# Power_Supply.net
KiCad netlist of a schematic drawn in Altium Designer
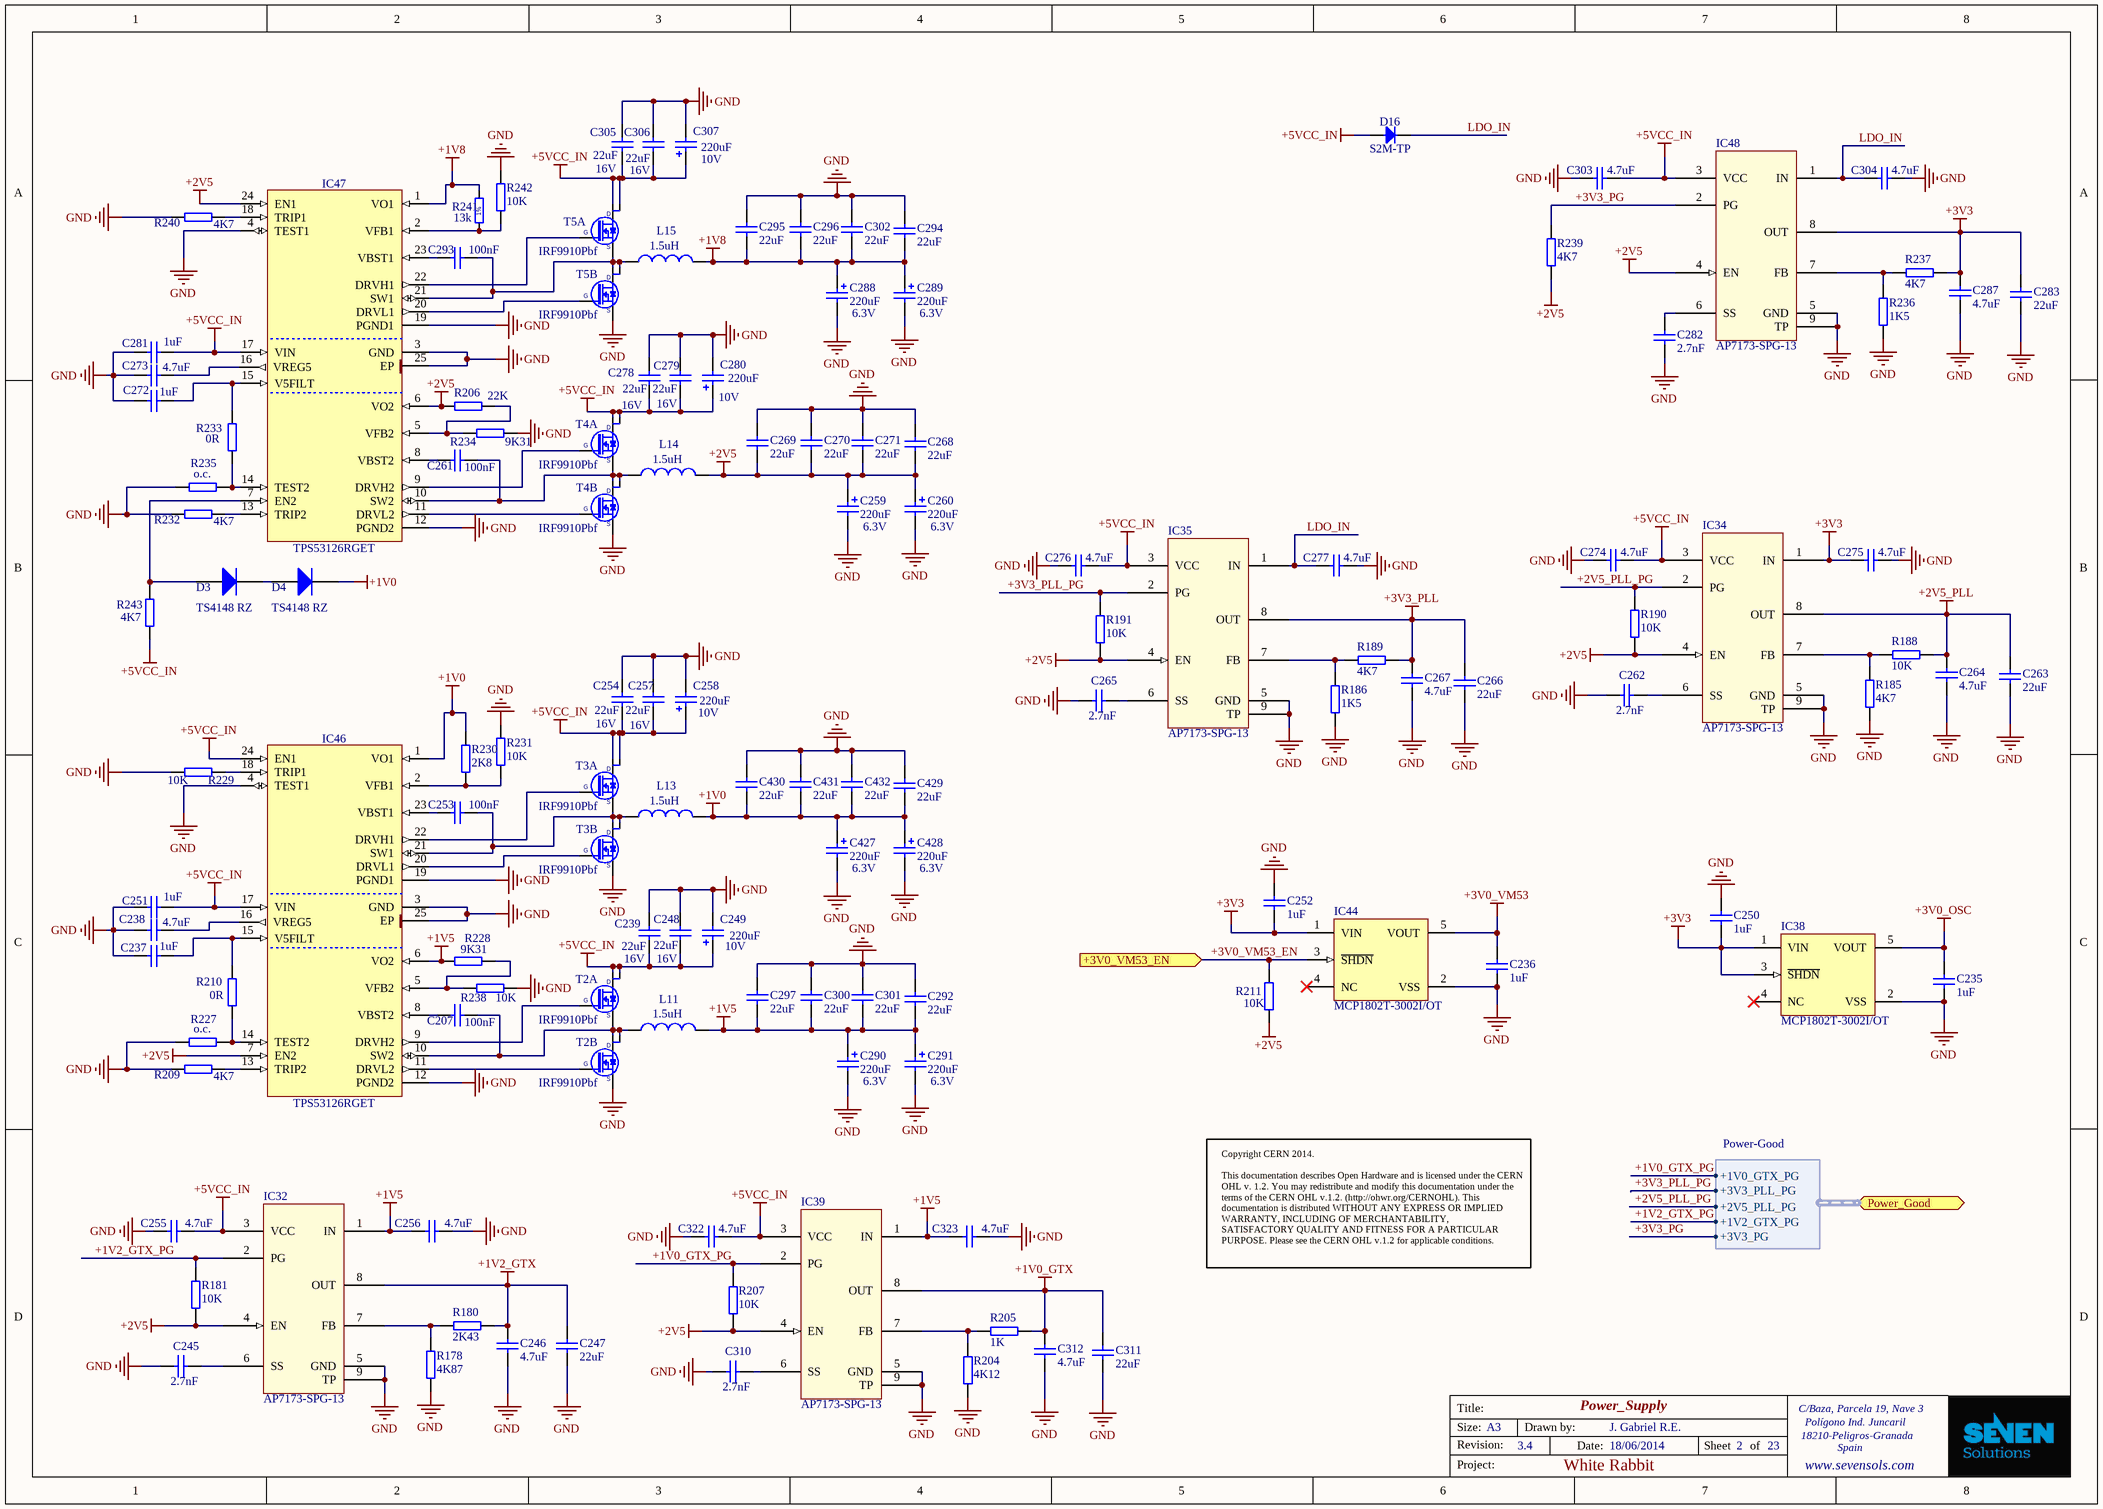
[diagram p0: Power_Supply.SchDoc]

(export (version "E")
  (design (tool "Eeschema 10.0.6"))
  (components
    (comp (ref "C207")
      (value "100nF")
      (footprint "CC1005-0402")
      (description "Capacitor")
      (fields
        (field (name "TOLERANCE") "±10%")
        (field (name "VOLTAGE") "16V")
        (field (name "PUBLISHER") "Altium Limited")
      )
      (libsource (lib "wr_switch") (part "Cap"))
    )
    (comp (ref "C235")
      (value "1uF")
      (footprint "CC1005-0402")
      (description "Capacitor")
      (fields
        (field (name "TOLERANCE") "±10%")
        (field (name "VOLTAGE") "16V")
        (field (name "PUBLISHER") "Altium Limited")
      )
      (libsource (lib "wr_switch") (part "Cap"))
    )
    (comp (ref "C236")
      (value "1uF")
      (footprint "CC1005-0402")
      (description "Capacitor")
      (fields
        (field (name "TOLERANCE") "±10%")
        (field (name "VOLTAGE") "16V")
        (field (name "PUBLISHER") "Altium Limited")
      )
      (libsource (lib "wr_switch") (part "Cap"))
    )
    (comp (ref "C237")
      (value "1uF")
      (footprint "CC1005-0402")
      (description "Capacitor")
      (fields
        (field (name "TOLERANCE") "±10%")
        (field (name "VOLTAGE") "16V")
        (field (name "PUBLISHER") "Altium Limited")
      )
      (libsource (lib "wr_switch") (part "Cap"))
    )
    (comp (ref "C238")
      (value "4.7uF")
      (footprint "CC1608-0603")
      (description "Capacitor")
      (fields
        (field (name "TOLERANCE") "±10%")
        (field (name "VOLTAGE") "10V")
        (field (name "PUBLISHER") "Altium Limited")
      )
      (libsource (lib "wr_switch") (part "Cap"))
    )
    (comp (ref "C239")
      (value "22uF")
      (footprint "CC2012-0805")
      (description "Capacitor")
      (fields
        (field (name "TOLERANCE") "±10%")
        (field (name "VOLTAGE") "16V")
        (field (name "Comment") "22uF 16V")
        (field (name "PUBLISHER") "Altium Limited")
      )
      (libsource (lib "wr_switch") (part "Cap"))
    )
    (comp (ref "C245")
      (value "2.7nF")
      (footprint "CC1005-0402")
      (description "Capacitor")
      (fields
        (field (name "TOLERANCE") "±10%")
        (field (name "VOLTAGE") "50V")
        (field (name "PUBLISHER") "Altium Limited")
      )
      (libsource (lib "wr_switch") (part "Cap"))
    )
    (comp (ref "C246")
      (value "4.7uF")
      (footprint "CC1608-0603")
      (description "Capacitor")
      (fields
        (field (name "TOLERANCE") "±10%")
        (field (name "VOLTAGE") "10V")
        (field (name "PUBLISHER") "Altium Limited")
      )
      (libsource (lib "wr_switch") (part "Cap"))
    )
    (comp (ref "C247")
      (value "22uF")
      (footprint "CC2012-0805")
      (description "Capacitor")
      (fields
        (field (name "TOLERANCE") "±20%")
        (field (name "VOLTAGE") "6.3V")
        (field (name "PUBLISHER") "Altium Limited")
      )
      (libsource (lib "wr_switch") (part "Cap"))
    )
    (comp (ref "C248")
      (value "22uF")
      (footprint "CC2012-0805")
      (description "Capacitor")
      (fields
        (field (name "TOLERANCE") "±10%")
        (field (name "VOLTAGE") "16V")
        (field (name "Comment") "22uF 16V")
        (field (name "PUBLISHER") "Altium Limited")
      )
      (libsource (lib "wr_switch") (part "Cap"))
    )
    (comp (ref "C249")
      (value "220uF")
      (footprint "D")
      (description "Polarized Capacitor Tantalum")
      (fields
        (field (name "TOLERANCE") "±20%")
        (field (name "VOLTAGE") "10V")
        (field (name "Comment") "220uF 10V")
        (field (name "PUBLISHER") "Altium Limited")
      )
      (libsource (lib "wr_switch") (part "Cap Pol1"))
    )
    (comp (ref "C250")
      (value "1uF")
      (footprint "CC1005-0402")
      (description "Capacitor")
      (fields
        (field (name "TOLERANCE") "±10%")
        (field (name "VOLTAGE") "16V")
        (field (name "PUBLISHER") "Altium Limited")
      )
      (libsource (lib "wr_switch") (part "Cap"))
    )
    (comp (ref "C251")
      (value "1uF")
      (footprint "CC1005-0402")
      (description "Capacitor")
      (fields
        (field (name "TOLERANCE") "±10%")
        (field (name "VOLTAGE") "16V")
        (field (name "PUBLISHER") "Altium Limited")
      )
      (libsource (lib "wr_switch") (part "Cap"))
    )
    (comp (ref "C252")
      (value "1uF")
      (footprint "CC1005-0402")
      (description "Capacitor")
      (fields
        (field (name "TOLERANCE") "±10%")
        (field (name "VOLTAGE") "16V")
        (field (name "PUBLISHER") "Altium Limited")
      )
      (libsource (lib "wr_switch") (part "Cap"))
    )
    (comp (ref "C253")
      (value "100nF")
      (footprint "CC1005-0402")
      (description "Capacitor")
      (fields
        (field (name "TOLERANCE") "±10%")
        (field (name "VOLTAGE") "16V")
        (field (name "PUBLISHER") "Altium Limited")
      )
      (libsource (lib "wr_switch") (part "Cap"))
    )
    (comp (ref "C254")
      (value "22uF")
      (footprint "CC2012-0805")
      (description "Capacitor")
      (fields
        (field (name "TOLERANCE") "±10%")
        (field (name "VOLTAGE") "16V")
        (field (name "Comment") "22uF 16V")
        (field (name "PUBLISHER") "Altium Limited")
      )
      (libsource (lib "wr_switch") (part "Cap"))
    )
    (comp (ref "C255")
      (value "4.7uF")
      (footprint "CC1608-0603")
      (description "Capacitor")
      (fields
        (field (name "TOLERANCE") "±10%")
        (field (name "VOLTAGE") "10V")
        (field (name "PUBLISHER") "Altium Limited")
      )
      (libsource (lib "wr_switch") (part "Cap"))
    )
    (comp (ref "C256")
      (value "4.7uF")
      (footprint "CC1608-0603")
      (description "Capacitor")
      (fields
        (field (name "TOLERANCE") "±10%")
        (field (name "VOLTAGE") "10V")
        (field (name "PUBLISHER") "Altium Limited")
      )
      (libsource (lib "wr_switch") (part "Cap"))
    )
    (comp (ref "C257")
      (value "22uF")
      (footprint "CC2012-0805")
      (description "Capacitor")
      (fields
        (field (name "TOLERANCE") "±10%")
        (field (name "VOLTAGE") "16V")
        (field (name "Comment") "22uF 16V")
        (field (name "PUBLISHER") "Altium Limited")
      )
      (libsource (lib "wr_switch") (part "Cap"))
    )
    (comp (ref "C258")
      (value "220uF")
      (footprint "D")
      (description "Polarized Capacitor Tantalum")
      (fields
        (field (name "TOLERANCE") "±20%")
        (field (name "VOLTAGE") "10V")
        (field (name "Comment") "220uF 10V")
        (field (name "PUBLISHER") "Altium Limited")
      )
      (libsource (lib "wr_switch") (part "Cap Pol1"))
    )
    (comp (ref "C259")
      (value "220uF")
      (footprint "D")
      (description "Polarized Capacitor Tantalum")
      (fields
        (field (name "TOLERANCE") "±20%")
        (field (name "VOLTAGE") "6.3V")
        (field (name "PUBLISHER") "Altium Limited")
      )
      (libsource (lib "wr_switch") (part "Cap Pol1"))
    )
    (comp (ref "C260")
      (value "220uF")
      (footprint "D")
      (description "Polarized Capacitor Tantalum")
      (fields
        (field (name "TOLERANCE") "±20%")
        (field (name "VOLTAGE") "6.3V")
        (field (name "PUBLISHER") "Altium Limited")
      )
      (libsource (lib "wr_switch") (part "Cap Pol1"))
    )
    (comp (ref "C261")
      (value "100nF")
      (footprint "CC1005-0402")
      (description "Capacitor")
      (fields
        (field (name "TOLERANCE") "±10%")
        (field (name "VOLTAGE") "16V")
        (field (name "PUBLISHER") "Altium Limited")
      )
      (libsource (lib "wr_switch") (part "Cap"))
    )
    (comp (ref "C262")
      (value "2.7nF")
      (footprint "CC1005-0402")
      (description "Capacitor")
      (fields
        (field (name "TOLERANCE") "±10%")
        (field (name "VOLTAGE") "50V")
        (field (name "PUBLISHER") "Altium Limited")
      )
      (libsource (lib "wr_switch") (part "Cap"))
    )
    (comp (ref "C263")
      (value "22uF")
      (footprint "CC2012-0805")
      (description "Capacitor")
      (fields
        (field (name "TOLERANCE") "±20%")
        (field (name "VOLTAGE") "6.3V")
        (field (name "PUBLISHER") "Altium Limited")
      )
      (libsource (lib "wr_switch") (part "Cap"))
    )
    (comp (ref "C264")
      (value "4.7uF")
      (footprint "CC1608-0603")
      (description "Capacitor")
      (fields
        (field (name "TOLERANCE") "±10%")
        (field (name "VOLTAGE") "10V")
        (field (name "PUBLISHER") "Altium Limited")
      )
      (libsource (lib "wr_switch") (part "Cap"))
    )
    (comp (ref "C265")
      (value "2.7nF")
      (footprint "CC1005-0402")
      (description "Capacitor")
      (fields
        (field (name "TOLERANCE") "±10%")
        (field (name "VOLTAGE") "50V")
        (field (name "PUBLISHER") "Altium Limited")
      )
      (libsource (lib "wr_switch") (part "Cap"))
    )
    (comp (ref "C266")
      (value "22uF")
      (footprint "CC2012-0805")
      (description "Capacitor")
      (fields
        (field (name "TOLERANCE") "±20%")
        (field (name "VOLTAGE") "6.3V")
        (field (name "PUBLISHER") "Altium Limited")
      )
      (libsource (lib "wr_switch") (part "Cap"))
    )
    (comp (ref "C267")
      (value "4.7uF")
      (footprint "CC1608-0603")
      (description "Capacitor")
      (fields
        (field (name "TOLERANCE") "±10%")
        (field (name "VOLTAGE") "10V")
        (field (name "PUBLISHER") "Altium Limited")
      )
      (libsource (lib "wr_switch") (part "Cap"))
    )
    (comp (ref "C268")
      (value "22uF")
      (footprint "CC2012-0805")
      (description "Capacitor")
      (fields
        (field (name "TOLERANCE") "±20%")
        (field (name "VOLTAGE") "6.3V")
        (field (name "PUBLISHER") "Altium Limited")
      )
      (libsource (lib "wr_switch") (part "Cap"))
    )
    (comp (ref "C269")
      (value "22uF")
      (footprint "CC2012-0805")
      (description "Capacitor")
      (fields
        (field (name "TOLERANCE") "±20%")
        (field (name "VOLTAGE") "6.3V")
        (field (name "PUBLISHER") "Altium Limited")
      )
      (libsource (lib "wr_switch") (part "Cap"))
    )
    (comp (ref "C270")
      (value "22uF")
      (footprint "CC2012-0805")
      (description "Capacitor")
      (fields
        (field (name "TOLERANCE") "±20%")
        (field (name "VOLTAGE") "6.3V")
        (field (name "PUBLISHER") "Altium Limited")
      )
      (libsource (lib "wr_switch") (part "Cap"))
    )
    (comp (ref "C271")
      (value "22uF")
      (footprint "CC2012-0805")
      (description "Capacitor")
      (fields
        (field (name "TOLERANCE") "±20%")
        (field (name "VOLTAGE") "6.3V")
        (field (name "PUBLISHER") "Altium Limited")
      )
      (libsource (lib "wr_switch") (part "Cap"))
    )
    (comp (ref "C272")
      (value "1uF")
      (footprint "CC1005-0402")
      (description "Capacitor")
      (fields
        (field (name "TOLERANCE") "±10%")
        (field (name "VOLTAGE") "16V")
        (field (name "PUBLISHER") "Altium Limited")
      )
      (libsource (lib "wr_switch") (part "Cap"))
    )
    (comp (ref "C273")
      (value "4.7uF")
      (footprint "CC1608-0603")
      (description "Capacitor")
      (fields
        (field (name "TOLERANCE") "±10%")
        (field (name "VOLTAGE") "10V")
        (field (name "PUBLISHER") "Altium Limited")
      )
      (libsource (lib "wr_switch") (part "Cap"))
    )
    (comp (ref "C274")
      (value "4.7uF")
      (footprint "CC1608-0603")
      (description "Capacitor")
      (fields
        (field (name "TOLERANCE") "±10%")
        (field (name "VOLTAGE") "10V")
        (field (name "PUBLISHER") "Altium Limited")
      )
      (libsource (lib "wr_switch") (part "Cap"))
    )
    (comp (ref "C275")
      (value "4.7uF")
      (footprint "CC1608-0603")
      (description "Capacitor")
      (fields
        (field (name "TOLERANCE") "±10%")
        (field (name "VOLTAGE") "10V")
        (field (name "PUBLISHER") "Altium Limited")
      )
      (libsource (lib "wr_switch") (part "Cap"))
    )
    (comp (ref "C276")
      (value "4.7uF")
      (footprint "CC1608-0603")
      (description "Capacitor")
      (fields
        (field (name "TOLERANCE") "±10%")
        (field (name "VOLTAGE") "10V")
        (field (name "PUBLISHER") "Altium Limited")
      )
      (libsource (lib "wr_switch") (part "Cap"))
    )
    (comp (ref "C277")
      (value "4.7uF")
      (footprint "CC1608-0603")
      (description "Capacitor")
      (fields
        (field (name "TOLERANCE") "±10%")
        (field (name "VOLTAGE") "10V")
        (field (name "PUBLISHER") "Altium Limited")
      )
      (libsource (lib "wr_switch") (part "Cap"))
    )
    (comp (ref "C278")
      (value "22uF")
      (footprint "CC2012-0805")
      (description "Capacitor")
      (fields
        (field (name "TOLERANCE") "±10%")
        (field (name "VOLTAGE") "16V")
        (field (name "Comment") "22uF 16V")
        (field (name "PUBLISHER") "Altium Limited")
      )
      (libsource (lib "wr_switch") (part "Cap"))
    )
    (comp (ref "C279")
      (value "22uF")
      (footprint "CC2012-0805")
      (description "Capacitor")
      (fields
        (field (name "TOLERANCE") "±10%")
        (field (name "VOLTAGE") "16V")
        (field (name "Comment") "22uF 16V")
        (field (name "PUBLISHER") "Altium Limited")
      )
      (libsource (lib "wr_switch") (part "Cap"))
    )
    (comp (ref "C280")
      (value "220uF")
      (footprint "D")
      (description "Polarized Capacitor Tantalum")
      (fields
        (field (name "TOLERANCE") "±20%")
        (field (name "VOLTAGE") "10V")
        (field (name "Comment") "220uF 10V")
        (field (name "PUBLISHER") "Altium Limited")
      )
      (libsource (lib "wr_switch") (part "Cap Pol1"))
    )
    (comp (ref "C281")
      (value "1uF")
      (footprint "CC1005-0402")
      (description "Capacitor")
      (fields
        (field (name "TOLERANCE") "±10%")
        (field (name "VOLTAGE") "16V")
        (field (name "PUBLISHER") "Altium Limited")
      )
      (libsource (lib "wr_switch") (part "Cap"))
    )
    (comp (ref "C282")
      (value "2.7nF")
      (footprint "CC1005-0402")
      (description "Capacitor")
      (fields
        (field (name "TOLERANCE") "±10%")
        (field (name "VOLTAGE") "50V")
        (field (name "PUBLISHER") "Altium Limited")
      )
      (libsource (lib "wr_switch") (part "Cap"))
    )
    (comp (ref "C283")
      (value "22uF")
      (footprint "CC2012-0805")
      (description "Capacitor")
      (fields
        (field (name "TOLERANCE") "±20%")
        (field (name "VOLTAGE") "6.3V")
        (field (name "PUBLISHER") "Altium Limited")
      )
      (libsource (lib "wr_switch") (part "Cap"))
    )
    (comp (ref "C287")
      (value "4.7uF")
      (footprint "CC1608-0603")
      (description "Capacitor")
      (fields
        (field (name "TOLERANCE") "±10%")
        (field (name "VOLTAGE") "10V")
        (field (name "PUBLISHER") "Altium Limited")
      )
      (libsource (lib "wr_switch") (part "Cap"))
    )
    (comp (ref "C288")
      (value "220uF")
      (footprint "D")
      (description "Polarized Capacitor Tantalum")
      (fields
        (field (name "TOLERANCE") "±20%")
        (field (name "VOLTAGE") "6.3V")
        (field (name "PUBLISHER") "Altium Limited")
      )
      (libsource (lib "wr_switch") (part "Cap Pol1"))
    )
    (comp (ref "C289")
      (value "220uF")
      (footprint "D")
      (description "Polarized Capacitor Tantalum")
      (fields
        (field (name "TOLERANCE") "±20%")
        (field (name "VOLTAGE") "6.3V")
        (field (name "PUBLISHER") "Altium Limited")
      )
      (libsource (lib "wr_switch") (part "Cap Pol1"))
    )
    (comp (ref "C290")
      (value "220uF")
      (footprint "D")
      (description "Polarized Capacitor Tantalum")
      (fields
        (field (name "TOLERANCE") "±20%")
        (field (name "VOLTAGE") "6.3V")
        (field (name "PUBLISHER") "Altium Limited")
      )
      (libsource (lib "wr_switch") (part "Cap Pol1"))
    )
    (comp (ref "C291")
      (value "220uF")
      (footprint "D")
      (description "Polarized Capacitor Tantalum")
      (fields
        (field (name "TOLERANCE") "±20%")
        (field (name "VOLTAGE") "6.3V")
        (field (name "PUBLISHER") "Altium Limited")
      )
      (libsource (lib "wr_switch") (part "Cap Pol1"))
    )
    (comp (ref "C292")
      (value "22uF")
      (footprint "CC2012-0805")
      (description "Capacitor")
      (fields
        (field (name "TOLERANCE") "±20%")
        (field (name "VOLTAGE") "6.3V")
        (field (name "PUBLISHER") "Altium Limited")
      )
      (libsource (lib "wr_switch") (part "Cap"))
    )
    (comp (ref "C293")
      (value "100nF")
      (footprint "CC1005-0402")
      (description "Capacitor")
      (fields
        (field (name "TOLERANCE") "±10%")
        (field (name "VOLTAGE") "16V")
        (field (name "PUBLISHER") "Altium Limited")
      )
      (libsource (lib "wr_switch") (part "Cap"))
    )
    (comp (ref "C294")
      (value "22uF")
      (footprint "CC2012-0805")
      (description "Capacitor")
      (fields
        (field (name "TOLERANCE") "±20%")
        (field (name "VOLTAGE") "6.3V")
        (field (name "PUBLISHER") "Altium Limited")
      )
      (libsource (lib "wr_switch") (part "Cap"))
    )
    (comp (ref "C295")
      (value "22uF")
      (footprint "CC2012-0805")
      (description "Capacitor")
      (fields
        (field (name "TOLERANCE") "±20%")
        (field (name "VOLTAGE") "6.3V")
        (field (name "PUBLISHER") "Altium Limited")
      )
      (libsource (lib "wr_switch") (part "Cap"))
    )
    (comp (ref "C296")
      (value "22uF")
      (footprint "CC2012-0805")
      (description "Capacitor")
      (fields
        (field (name "TOLERANCE") "±20%")
        (field (name "VOLTAGE") "6.3V")
        (field (name "PUBLISHER") "Altium Limited")
      )
      (libsource (lib "wr_switch") (part "Cap"))
    )
    (comp (ref "C297")
      (value "22uF")
      (footprint "CC2012-0805")
      (description "Capacitor")
      (fields
        (field (name "TOLERANCE") "±20%")
        (field (name "VOLTAGE") "6.3V")
        (field (name "PUBLISHER") "Altium Limited")
      )
      (libsource (lib "wr_switch") (part "Cap"))
    )
    (comp (ref "C300")
      (value "22uF")
      (footprint "CC2012-0805")
      (description "Capacitor")
      (fields
        (field (name "TOLERANCE") "±20%")
        (field (name "VOLTAGE") "6.3V")
        (field (name "PUBLISHER") "Altium Limited")
      )
      (libsource (lib "wr_switch") (part "Cap"))
    )
    (comp (ref "C301")
      (value "22uF")
      (footprint "CC2012-0805")
      (description "Capacitor")
      (fields
        (field (name "TOLERANCE") "±20%")
        (field (name "VOLTAGE") "6.3V")
        (field (name "PUBLISHER") "Altium Limited")
      )
      (libsource (lib "wr_switch") (part "Cap"))
    )
    (comp (ref "C302")
      (value "22uF")
      (footprint "CC2012-0805")
      (description "Capacitor")
      (fields
        (field (name "TOLERANCE") "±20%")
        (field (name "VOLTAGE") "6.3V")
        (field (name "PUBLISHER") "Altium Limited")
      )
      (libsource (lib "wr_switch") (part "Cap"))
    )
    (comp (ref "C303")
      (value "4.7uF")
      (footprint "CC1608-0603")
      (description "Capacitor")
      (fields
        (field (name "TOLERANCE") "±10%")
        (field (name "VOLTAGE") "10V")
        (field (name "PUBLISHER") "Altium Limited")
      )
      (libsource (lib "wr_switch") (part "Cap"))
    )
    (comp (ref "C304")
      (value "4.7uF")
      (footprint "CC1608-0603")
      (description "Capacitor")
      (fields
        (field (name "TOLERANCE") "±10%")
        (field (name "VOLTAGE") "10V")
        (field (name "PUBLISHER") "Altium Limited")
      )
      (libsource (lib "wr_switch") (part "Cap"))
    )
    (comp (ref "C305")
      (value "22uF")
      (footprint "CC2012-0805")
      (description "Capacitor")
      (fields
        (field (name "TOLERANCE") "±10%")
        (field (name "VOLTAGE") "16V")
        (field (name "Comment") "22uF 16V")
        (field (name "PUBLISHER") "Altium Limited")
      )
      (libsource (lib "wr_switch") (part "Cap"))
    )
    (comp (ref "C306")
      (value "22uF")
      (footprint "CC2012-0805")
      (description "Capacitor")
      (fields
        (field (name "TOLERANCE") "±10%")
        (field (name "VOLTAGE") "16V")
        (field (name "Comment") "22uF 16V")
        (field (name "PUBLISHER") "Altium Limited")
      )
      (libsource (lib "wr_switch") (part "Cap"))
    )
    (comp (ref "C307")
      (value "220uF")
      (footprint "D")
      (description "Polarized Capacitor Tantalum")
      (fields
        (field (name "TOLERANCE") "±20%")
        (field (name "VOLTAGE") "10V")
        (field (name "Comment") "220uF 10V")
        (field (name "PUBLISHER") "Altium Limited")
      )
      (libsource (lib "wr_switch") (part "Cap Pol1"))
    )
    (comp (ref "C310")
      (value "2.7nF")
      (footprint "CC1005-0402")
      (description "Capacitor")
      (fields
        (field (name "TOLERANCE") "±10%")
        (field (name "VOLTAGE") "50V")
        (field (name "PUBLISHER") "Altium Limited")
      )
      (libsource (lib "wr_switch") (part "Cap"))
    )
    (comp (ref "C311")
      (value "22uF")
      (footprint "CC2012-0805")
      (description "Capacitor")
      (fields
        (field (name "TOLERANCE") "±20%")
        (field (name "VOLTAGE") "6.3V")
        (field (name "PUBLISHER") "Altium Limited")
      )
      (libsource (lib "wr_switch") (part "Cap"))
    )
    (comp (ref "C312")
      (value "4.7uF")
      (footprint "CC1608-0603")
      (description "Capacitor")
      (fields
        (field (name "TOLERANCE") "±10%")
        (field (name "VOLTAGE") "10V")
        (field (name "PUBLISHER") "Altium Limited")
      )
      (libsource (lib "wr_switch") (part "Cap"))
    )
    (comp (ref "C322")
      (value "4.7uF")
      (footprint "CC1608-0603")
      (description "Capacitor")
      (fields
        (field (name "TOLERANCE") "±10%")
        (field (name "VOLTAGE") "10V")
        (field (name "PUBLISHER") "Altium Limited")
      )
      (libsource (lib "wr_switch") (part "Cap"))
    )
    (comp (ref "C323")
      (value "4.7uF")
      (footprint "CC1608-0603")
      (description "Capacitor")
      (fields
        (field (name "TOLERANCE") "±10%")
        (field (name "VOLTAGE") "10V")
        (field (name "PUBLISHER") "Altium Limited")
      )
      (libsource (lib "wr_switch") (part "Cap"))
    )
    (comp (ref "C427")
      (value "220uF")
      (footprint "D")
      (description "Polarized Capacitor Tantalum")
      (fields
        (field (name "TOLERANCE") "±20%")
        (field (name "VOLTAGE") "6.3V")
        (field (name "PUBLISHER") "Altium Limited")
      )
      (libsource (lib "wr_switch") (part "Cap Pol1"))
    )
    (comp (ref "C428")
      (value "220uF")
      (footprint "D")
      (description "Polarized Capacitor Tantalum")
      (fields
        (field (name "TOLERANCE") "±20%")
        (field (name "VOLTAGE") "6.3V")
        (field (name "PUBLISHER") "Altium Limited")
      )
      (libsource (lib "wr_switch") (part "Cap Pol1"))
    )
    (comp (ref "C429")
      (value "22uF")
      (footprint "CC2012-0805")
      (description "Capacitor")
      (fields
        (field (name "TOLERANCE") "±20%")
        (field (name "VOLTAGE") "6.3V")
        (field (name "PUBLISHER") "Altium Limited")
      )
      (libsource (lib "wr_switch") (part "Cap"))
    )
    (comp (ref "C430")
      (value "22uF")
      (footprint "CC2012-0805")
      (description "Capacitor")
      (fields
        (field (name "TOLERANCE") "±20%")
        (field (name "VOLTAGE") "6.3V")
        (field (name "PUBLISHER") "Altium Limited")
      )
      (libsource (lib "wr_switch") (part "Cap"))
    )
    (comp (ref "C431")
      (value "22uF")
      (footprint "CC2012-0805")
      (description "Capacitor")
      (fields
        (field (name "TOLERANCE") "±20%")
        (field (name "VOLTAGE") "6.3V")
        (field (name "PUBLISHER") "Altium Limited")
      )
      (libsource (lib "wr_switch") (part "Cap"))
    )
    (comp (ref "C432")
      (value "22uF")
      (footprint "CC2012-0805")
      (description "Capacitor")
      (fields
        (field (name "TOLERANCE") "±20%")
        (field (name "VOLTAGE") "6.3V")
        (field (name "PUBLISHER") "Altium Limited")
      )
      (libsource (lib "wr_switch") (part "Cap"))
    )
    (comp (ref "D3")
      (value "TS4148 RZ")
      (footprint "CD1608-0603")
      (description "Default Diode")
      (fields (field (name "PUBLISHER") "Altium Limited"))
      (libsource (lib "Miscellaneous Devices") (part "Diode"))
    )
    (comp (ref "D4")
      (value "TS4148 RZ")
      (footprint "CD1608-0603")
      (description "Default Diode")
      (fields (field (name "PUBLISHER") "Altium Limited"))
      (libsource (lib "Miscellaneous Devices") (part "Diode"))
    )
    (comp (ref "D16")
      (value "S2M-TP")
      (footprint "DO-214AA/SMB-MCC")
      (description "2 A Silicon Rectifier 50 to 1000 Volts")
      (fields (field (name "AUTHOR") "CERN DEM JLC"))
      (libsource (lib "wr_switch") (part "S2M-TP"))
    )
    (comp (ref "IC32")
      (value "AP7173-SPG-13")
      (footprint "7S_WR:SOIC127P600-8AL-ThermalPad")
      (description "1.5A Low Dropout Linera Regulator")
      (libsource (lib "SCB") (part "AP7173"))
    )
    (comp (ref "IC34")
      (value "AP7173-SPG-13")
      (footprint "7S_WR:SOIC127P600-8AL-ThermalPad")
      (description "1.5A Low Dropout Linera Regulator")
      (libsource (lib "SCB") (part "AP7173"))
    )
    (comp (ref "IC35")
      (value "AP7173-SPG-13")
      (footprint "7S_WR:SOIC127P600-8AL-ThermalPad")
      (description "1.5A Low Dropout Linera Regulator")
      (libsource (lib "SCB") (part "AP7173"))
    )
    (comp (ref "IC38")
      (value "MCP1802T-3002I/OT")
      (footprint "SOT-23-OT5_N")
      (description "300 mA, High PSRR, Low Quiescent Current LDO, 5-Pin SOT-23, Industrial Temperature, Tape and Reel")
      (fields (field (name "PUBLISHER") "Altium Limited"))
      (libsource (lib "Microchip Power Mgt Line Regulator") (part "MCP1802T-3002I/OT"))
    )
    (comp (ref "IC39")
      (value "AP7173-SPG-13")
      (footprint "7S_WR:SOIC127P600-8AL-ThermalPad")
      (description "1.5A Low Dropout Linera Regulator")
      (libsource (lib "SCB") (part "AP7173"))
    )
    (comp (ref "IC44")
      (value "MCP1802T-3002I/OT")
      (footprint "SOT-23-OT5_N")
      (description "300 mA, High PSRR, Low Quiescent Current LDO, 5-Pin SOT-23, Industrial Temperature, Tape and Reel")
      (fields (field (name "PUBLISHER") "Altium Limited"))
      (libsource (lib "Microchip Power Mgt Line Regulator") (part "MCP1802T-3002I/OT"))
    )
    (comp (ref "IC46")
      (value "TPS53126RGET")
      (footprint "QFN50P400X400X100-25N-S255")
      (description "Dual Synchronous Step-Down Controller For Low Voltage Power Rails")
      (fields (field (name "MANUFACTURER") "TEXAS INSTRUMENTS") (field (name "AUTHOR") "CERN DEM JLC"))
      (libsource (lib "wr_switch") (part "TPS53126RGET"))
    )
    (comp (ref "IC47")
      (value "TPS53126RGET")
      (footprint "QFN50P400X400X100-25N-S255")
      (description "Dual Synchronous Step-Down Controller For Low Voltage Power Rails")
      (fields (field (name "MANUFACTURER") "TEXAS INSTRUMENTS") (field (name "AUTHOR") "CERN DEM JLC"))
      (libsource (lib "wr_switch") (part "TPS53126RGET"))
    )
    (comp (ref "IC48")
      (value "AP7173-SPG-13")
      (footprint "7S_WR:SOIC127P600-8AL-ThermalPad")
      (description "1.5A Low Dropout Linera Regulator")
      (libsource (lib "SCB") (part "AP7173"))
    )
    (comp (ref "L11")
      (value "1.5uH")
      (footprint "IHLP2525")
      (description "Low Profile, High Current Inductor")
      (fields
        (field (name "MANUFACTURER") "Vishay/Dale")
        (field (name "Comment") "IHLP2525CZER1R5M01")
        (field (name "PUBLISHER") "Altium Limited")
      )
      (libsource (lib "Miscellaneous Devices") (part "Inductor"))
    )
    (comp (ref "L13")
      (value "1.5uH")
      (footprint "IHLP2525")
      (description "Low Profile, High Current Inductor")
      (fields
        (field (name "MANUFACTURER") "Vishay/Dale")
        (field (name "Comment") "IHLP2525CZER1R5M01")
        (field (name "PUBLISHER") "Altium Limited")
      )
      (libsource (lib "Miscellaneous Devices") (part "Inductor"))
    )
    (comp (ref "L14")
      (value "1.5uH")
      (footprint "IHLP2525")
      (description "Low Profile, High Current Inductor")
      (fields
        (field (name "MANUFACTURER") "Vishay/Dale")
        (field (name "Comment") "IHLP2525CZER1R5M01")
        (field (name "PUBLISHER") "Altium Limited")
      )
      (libsource (lib "Miscellaneous Devices") (part "Inductor"))
    )
    (comp (ref "L15")
      (value "1.5uH")
      (footprint "IHLP2525")
      (description "Low Profile, High Current Inductor")
      (fields
        (field (name "MANUFACTURER") "Vishay/Dale")
        (field (name "Comment") "IHLP2525CZER1R5M01")
        (field (name "PUBLISHER") "Altium Limited")
      )
      (libsource (lib "Miscellaneous Devices") (part "Inductor"))
    )
    (comp (ref "R178")
      (value "4K87")
      (footprint "0402")
      (description "SMD Resistor")
      (fields (field (name "TOLERANCE") "±1%"))
      (libsource (lib "wr_switch") (part "RES_SMD"))
    )
    (comp (ref "R180")
      (value "2K43")
      (footprint "0402")
      (description "SMD Resistor")
      (fields (field (name "TOLERANCE") "±1%"))
      (libsource (lib "wr_switch") (part "RES_SMD"))
    )
    (comp (ref "R181")
      (value "10K")
      (footprint "0402")
      (description "SMD Resistor")
      (fields (field (name "TOLERANCE") "±1%") (field (name "Comment") "10k"))
      (libsource (lib "wr_switch") (part "RES_SMD"))
    )
    (comp (ref "R185")
      (value "4K7")
      (footprint "0402")
      (description "SMD Resistor")
      (fields (field (name "TOLERANCE") "±1%"))
      (libsource (lib "wr_switch") (part "RES_SMD"))
    )
    (comp (ref "R186")
      (value "1K5")
      (footprint "0402")
      (description "SMD Resistor")
      (fields (field (name "TOLERANCE") "±1%"))
      (libsource (lib "wr_switch") (part "RES_SMD"))
    )
    (comp (ref "R188")
      (value "10K")
      (footprint "0402")
      (description "SMD Resistor")
      (fields (field (name "TOLERANCE") "±1%"))
      (libsource (lib "wr_switch") (part "RES_SMD"))
    )
    (comp (ref "R189")
      (value "4K7")
      (footprint "0402")
      (description "SMD Resistor")
      (fields (field (name "TOLERANCE") "±1%"))
      (libsource (lib "wr_switch") (part "RES_SMD"))
    )
    (comp (ref "R190")
      (value "10K")
      (footprint "0402")
      (description "SMD Resistor")
      (fields (field (name "TOLERANCE") "±1%") (field (name "Comment") "10k"))
      (libsource (lib "wr_switch") (part "RES_SMD"))
    )
    (comp (ref "R191")
      (value "10K")
      (footprint "0402")
      (description "SMD Resistor")
      (fields (field (name "TOLERANCE") "±1%") (field (name "Comment") "10k"))
      (libsource (lib "wr_switch") (part "RES_SMD"))
    )
    (comp (ref "R204")
      (value "4K12")
      (footprint "0402")
      (description "SMD Resistor")
      (fields (field (name "TOLERANCE") "±1%"))
      (libsource (lib "wr_switch") (part "RES_SMD"))
    )
    (comp (ref "R205")
      (value "1K")
      (footprint "0402")
      (description "SMD Resistor")
      (fields (field (name "TOLERANCE") "±1%"))
      (libsource (lib "wr_switch") (part "RES_SMD"))
    )
    (comp (ref "R206")
      (value "22K")
      (footprint "0402")
      (description "SMD Resistor")
      (fields (field (name "TOLERANCE") "±1%"))
      (libsource (lib "wr_switch") (part "RES_SMD"))
    )
    (comp (ref "R207")
      (value "10K")
      (footprint "0402")
      (description "SMD Resistor")
      (fields (field (name "TOLERANCE") "±1%"))
      (libsource (lib "wr_switch") (part "RES_SMD"))
    )
    (comp (ref "R209")
      (value "4K7")
      (footprint "0402")
      (description "SMD Resistor")
      (fields (field (name "TOLERANCE") "±1%"))
      (libsource (lib "wr_switch") (part "RES_SMD"))
    )
    (comp (ref "R210")
      (value "0R")
      (footprint "0402")
      (description "SMD Resistor")
      (fields (field (name "TOLERANCE") "Jumper"))
      (libsource (lib "wr_switch") (part "RES_SMD"))
    )
    (comp (ref "R211")
      (value "10K")
      (footprint "0402")
      (description "SMD Resistor")
      (fields (field (name "TOLERANCE") "±1%") (field (name "Comment") "10k"))
      (libsource (lib "wr_switch") (part "RES_SMD"))
    )
    (comp (ref "R227")
      (value "o.c.")
      (footprint "0402")
      (description "SMD Resistor")
      (libsource (lib "wr_switch") (part "RES_SMD"))
    )
    (comp (ref "R228")
      (value "9K31")
      (footprint "0402")
      (description "SMD Resistor")
      (fields (field (name "TOLERANCE") "±1%"))
      (libsource (lib "wr_switch") (part "RES_SMD"))
    )
    (comp (ref "R229")
      (value "10K")
      (footprint "0402")
      (description "SMD Resistor")
      (fields (field (name "TOLERANCE") "±1%"))
      (libsource (lib "wr_switch") (part "RES_SMD"))
    )
    (comp (ref "R230")
      (value "2K8")
      (footprint "0402")
      (description "SMD Resistor")
      (fields (field (name "TOLERANCE") "±1%"))
      (libsource (lib "wr_switch") (part "RES_SMD"))
    )
    (comp (ref "R231")
      (value "10K")
      (footprint "0402")
      (description "SMD Resistor")
      (fields (field (name "TOLERANCE") "±1%"))
      (libsource (lib "wr_switch") (part "RES_SMD"))
    )
    (comp (ref "R232")
      (value "4K7")
      (footprint "0402")
      (description "SMD Resistor")
      (fields (field (name "TOLERANCE") "±1%"))
      (libsource (lib "wr_switch") (part "RES_SMD"))
    )
    (comp (ref "R233")
      (value "0R")
      (footprint "0402")
      (description "SMD Resistor")
      (fields (field (name "TOLERANCE") "Jumper"))
      (libsource (lib "wr_switch") (part "RES_SMD"))
    )
    (comp (ref "R234")
      (value "9K31")
      (footprint "0402")
      (description "SMD Resistor")
      (fields (field (name "TOLERANCE") "±1%"))
      (libsource (lib "wr_switch") (part "RES_SMD"))
    )
    (comp (ref "R235")
      (value "o.c.")
      (footprint "0402")
      (description "SMD Resistor")
      (libsource (lib "wr_switch") (part "RES_SMD"))
    )
    (comp (ref "R236")
      (value "1K5")
      (footprint "0402")
      (description "SMD Resistor")
      (fields (field (name "TOLERANCE") "±1%"))
      (libsource (lib "wr_switch") (part "RES_SMD"))
    )
    (comp (ref "R237")
      (value "4K7")
      (footprint "0402")
      (description "SMD Resistor")
      (fields (field (name "TOLERANCE") "±1%"))
      (libsource (lib "wr_switch") (part "RES_SMD"))
    )
    (comp (ref "R238")
      (value "10K")
      (footprint "0402")
      (description "SMD Resistor")
      (fields (field (name "TOLERANCE") "±1%"))
      (libsource (lib "wr_switch") (part "RES_SMD"))
    )
    (comp (ref "R239")
      (value "4K7")
      (footprint "0402")
      (description "SMD Resistor")
      (fields (field (name "TOLERANCE") "±1%"))
      (libsource (lib "wr_switch") (part "RES_SMD"))
    )
    (comp (ref "R240")
      (value "4K7")
      (footprint "0402")
      (description "SMD Resistor")
      (fields (field (name "TOLERANCE") "±1%"))
      (libsource (lib "wr_switch") (part "RES_SMD"))
    )
    (comp (ref "R241")
      (value "13k")
      (footprint "RESC1005X40N")
      (description "Resistor - 1%")
      (fields
        (field (name "PART NUMBER") "R0402_13K_1%_0.0625W_100PPM")
        (field (name "POWER") "0.0625W")
        (field (name "AUTHOR") "CERN DEM JLC")
      )
      (libsource (lib "Resistors") (part "Resistor - 1%"))
    )
    (comp (ref "R242")
      (value "10K")
      (footprint "0402")
      (description "SMD Resistor")
      (fields (field (name "TOLERANCE") "±1%"))
      (libsource (lib "wr_switch") (part "RES_SMD"))
    )
    (comp (ref "R243")
      (value "4K7")
      (footprint "0402")
      (description "SMD Resistor")
      (fields (field (name "TOLERANCE") "±1%"))
      (libsource (lib "wr_switch") (part "RES_SMD"))
    )
    (comp (ref "T2")
      (value "IRF9910Pbf")
      (footprint "SOIC127P600X175-8N")
      (description "Dual SO-8 MOSFET For POL Cconverter")
      (fields (field (name "MANUFACTURER") "INTERNATIONAL RECTIFIER") (field (name "AUTHOR") "CERN DEM JLC"))
      (libsource (lib "ICs And Semiconductors") (part "IRF9910"))
    )
    (comp (ref "T3")
      (value "IRF9910Pbf")
      (footprint "SOIC127P600X175-8N")
      (description "Dual SO-8 MOSFET For POL Cconverter")
      (fields (field (name "MANUFACTURER") "INTERNATIONAL RECTIFIER") (field (name "AUTHOR") "CERN DEM JLC"))
      (libsource (lib "ICs And Semiconductors") (part "IRF9910"))
    )
    (comp (ref "T4")
      (value "IRF9910Pbf")
      (footprint "SOIC127P600X175-8N")
      (description "Dual SO-8 MOSFET For POL Cconverter")
      (fields (field (name "MANUFACTURER") "INTERNATIONAL RECTIFIER") (field (name "AUTHOR") "CERN DEM JLC"))
      (libsource (lib "ICs And Semiconductors") (part "IRF9910"))
    )
    (comp (ref "T5")
      (value "IRF9910Pbf")
      (footprint "SOIC127P600X175-8N")
      (description "Dual SO-8 MOSFET For POL Cconverter")
      (fields (field (name "MANUFACTURER") "INTERNATIONAL RECTIFIER") (field (name "AUTHOR") "CERN DEM JLC"))
      (libsource (lib "ICs And Semiconductors") (part "IRF9910"))
    )
  )
  (nets
    (net (code "2") (name "+1V0") (class "Default")
      (node (ref "C427") (pin "1") (pinfunction "1_1") (pintype "passive"))
      (node (ref "C428") (pin "1") (pinfunction "1_1") (pintype "passive"))
      (node (ref "C429") (pin "1") (pinfunction "1_1") (pintype "passive"))
      (node (ref "C430") (pin "2") (pinfunction "2_2") (pintype "passive"))
      (node (ref "C431") (pin "1") (pinfunction "1_1") (pintype "passive"))
      (node (ref "C432") (pin "1") (pinfunction "1_1") (pintype "passive"))
      (node (ref "D4") (pin "2") (pinfunction "K_2") (pintype "passive"))
      (node (ref "IC46") (pin "1") (pinfunction "VO1_1") (pintype "input"))
      (node (ref "L13") (pin "2") (pinfunction "2_2") (pintype "passive"))
      (node (ref "R230") (pin "2") (pinfunction "2_2") (pintype "passive"))
    )
    (net (code "3") (name "+1V0_GTX") (class "Default")
      (node (ref "C311") (pin "2") (pinfunction "2_2") (pintype "passive"))
      (node (ref "C312") (pin "2") (pinfunction "2_2") (pintype "passive"))
      (node (ref "IC39") (pin "8") (pinfunction "OUT_8") (pintype "power_in"))
      (node (ref "R205") (pin "2") (pinfunction "2_2") (pintype "passive"))
    )
    (net (code "4") (name "+1V2_GTX") (class "Default")
      (node (ref "C246") (pin "2") (pinfunction "2_2") (pintype "passive"))
      (node (ref "C247") (pin "2") (pinfunction "2_2") (pintype "passive"))
      (node (ref "IC32") (pin "8") (pinfunction "OUT_8") (pintype "power_in"))
      (node (ref "R180") (pin "2") (pinfunction "2_2") (pintype "passive"))
    )
    (net (code "5") (name "+1V5") (class "Default")
      (node (ref "C256") (pin "1") (pinfunction "1_1") (pintype "passive"))
      (node (ref "C290") (pin "1") (pinfunction "1_1") (pintype "passive"))
      (node (ref "C291") (pin "1") (pinfunction "1_1") (pintype "passive"))
      (node (ref "C292") (pin "1") (pinfunction "1_1") (pintype "passive"))
      (node (ref "C297") (pin "2") (pinfunction "2_2") (pintype "passive"))
      (node (ref "C300") (pin "1") (pinfunction "1_1") (pintype "passive"))
      (node (ref "C301") (pin "1") (pinfunction "1_1") (pintype "passive"))
      (node (ref "C323") (pin "1") (pinfunction "1_1") (pintype "passive"))
      (node (ref "IC32") (pin "1") (pinfunction "IN_1") (pintype "power_in"))
      (node (ref "IC39") (pin "1") (pinfunction "IN_1") (pintype "power_in"))
      (node (ref "IC46") (pin "6") (pinfunction "VO2_6") (pintype "input"))
      (node (ref "L11") (pin "2") (pinfunction "2_2") (pintype "passive"))
      (node (ref "R228") (pin "1") (pinfunction "1_1") (pintype "passive"))
    )
    (net (code "6") (name "+1V8") (class "Default")
      (node (ref "C288") (pin "1") (pinfunction "1_1") (pintype "passive"))
      (node (ref "C289") (pin "1") (pinfunction "1_1") (pintype "passive"))
      (node (ref "C294") (pin "1") (pinfunction "1_1") (pintype "passive"))
      (node (ref "C295") (pin "2") (pinfunction "2_2") (pintype "passive"))
      (node (ref "C296") (pin "1") (pinfunction "1_1") (pintype "passive"))
      (node (ref "C302") (pin "1") (pinfunction "1_1") (pintype "passive"))
      (node (ref "IC47") (pin "1") (pinfunction "VO1_1") (pintype "input"))
      (node (ref "L15") (pin "2") (pinfunction "2_2") (pintype "passive"))
      (node (ref "R241") (pin "2") (pinfunction "2_2") (pintype "passive"))
    )
    (net (code "7") (name "+2V5") (class "Default")
      (node (ref "C259") (pin "1") (pinfunction "1_1") (pintype "passive"))
      (node (ref "C260") (pin "1") (pinfunction "1_1") (pintype "passive"))
      (node (ref "C268") (pin "1") (pinfunction "1_1") (pintype "passive"))
      (node (ref "C269") (pin "2") (pinfunction "2_2") (pintype "passive"))
      (node (ref "C270") (pin "1") (pinfunction "1_1") (pintype "passive"))
      (node (ref "C271") (pin "1") (pinfunction "1_1") (pintype "passive"))
      (node (ref "IC32") (pin "4") (pinfunction "EN_4") (pintype "input"))
      (node (ref "IC34") (pin "4") (pinfunction "EN_4") (pintype "input"))
      (node (ref "IC35") (pin "4") (pinfunction "EN_4") (pintype "input"))
      (node (ref "IC39") (pin "4") (pinfunction "EN_4") (pintype "input"))
      (node (ref "IC46") (pin "7") (pinfunction "EN2_7") (pintype "input"))
      (node (ref "IC47") (pin "24") (pinfunction "EN1_24") (pintype "input"))
      (node (ref "IC47") (pin "6") (pinfunction "VO2_6") (pintype "input"))
      (node (ref "IC48") (pin "4") (pinfunction "EN_4") (pintype "input"))
      (node (ref "L14") (pin "2") (pinfunction "2_2") (pintype "passive"))
      (node (ref "R181") (pin "1") (pinfunction "1_1") (pintype "passive"))
      (node (ref "R190") (pin "1") (pinfunction "1_1") (pintype "passive"))
      (node (ref "R191") (pin "1") (pinfunction "1_1") (pintype "passive"))
      (node (ref "R206") (pin "2") (pinfunction "2_2") (pintype "passive"))
      (node (ref "R207") (pin "1") (pinfunction "1_1") (pintype "passive"))
      (node (ref "R211") (pin "2") (pinfunction "2_2") (pintype "passive"))
      (node (ref "R239") (pin "1") (pinfunction "1_1") (pintype "passive"))
    )
    (net (code "8") (name "+2V5_PLL") (class "Default")
      (node (ref "C263") (pin "2") (pinfunction "2_2") (pintype "passive"))
      (node (ref "C264") (pin "2") (pinfunction "2_2") (pintype "passive"))
      (node (ref "IC34") (pin "8") (pinfunction "OUT_8") (pintype "power_in"))
      (node (ref "R188") (pin "1") (pinfunction "1_1") (pintype "passive"))
    )
    (net (code "9") (name "+3V0_OSC") (class "Default")
      (node (ref "C235") (pin "2") (pinfunction "2_2") (pintype "passive"))
      (node (ref "IC38") (pin "5") (pinfunction "VOUT_5") (pintype "power_in"))
    )
    (net (code "10") (name "+3V0_VM53") (class "Default")
      (node (ref "C236") (pin "2") (pinfunction "2_2") (pintype "passive"))
      (node (ref "IC44") (pin "5") (pinfunction "VOUT_5") (pintype "power_in"))
    )
    (net (code "11") (name "+3V3") (class "Default")
      (node (ref "C250") (pin "2") (pinfunction "2_2") (pintype "passive"))
      (node (ref "C252") (pin "2") (pinfunction "2_2") (pintype "passive"))
      (node (ref "C275") (pin "1") (pinfunction "1_1") (pintype "passive"))
      (node (ref "C283") (pin "2") (pinfunction "2_2") (pintype "passive"))
      (node (ref "C287") (pin "2") (pinfunction "2_2") (pintype "passive"))
      (node (ref "IC34") (pin "1") (pinfunction "IN_1") (pintype "power_in"))
      (node (ref "IC38") (pin "1") (pinfunction "VIN_1") (pintype "power_in"))
      (node (ref "IC38") (pin "3") (pinfunction "~{SHDN}_3") (pintype "input"))
      (node (ref "IC44") (pin "1") (pinfunction "VIN_1") (pintype "power_in"))
      (node (ref "IC48") (pin "8") (pinfunction "OUT_8") (pintype "power_in"))
      (node (ref "R237") (pin "2") (pinfunction "2_2") (pintype "passive"))
    )
    (net (code "12") (name "+3V3_PLL") (class "Default")
      (node (ref "C266") (pin "2") (pinfunction "2_2") (pintype "passive"))
      (node (ref "C267") (pin "2") (pinfunction "2_2") (pintype "passive"))
      (node (ref "IC35") (pin "8") (pinfunction "OUT_8") (pintype "power_in"))
      (node (ref "R189") (pin "1") (pinfunction "1_1") (pintype "passive"))
    )
    (net (code "13") (name "+5VCC_IN") (class "Default")
      (node (ref "C239") (pin "1") (pinfunction "1_1") (pintype "passive"))
      (node (ref "C248") (pin "1") (pinfunction "1_1") (pintype "passive"))
      (node (ref "C249") (pin "1") (pinfunction "1_1") (pintype "passive"))
      (node (ref "C251") (pin "2") (pinfunction "2_2") (pintype "passive"))
      (node (ref "C254") (pin "1") (pinfunction "1_1") (pintype "passive"))
      (node (ref "C255") (pin "2") (pinfunction "2_2") (pintype "passive"))
      (node (ref "C257") (pin "1") (pinfunction "1_1") (pintype "passive"))
      (node (ref "C258") (pin "1") (pinfunction "1_1") (pintype "passive"))
      (node (ref "C274") (pin "2") (pinfunction "2_2") (pintype "passive"))
      (node (ref "C276") (pin "2") (pinfunction "2_2") (pintype "passive"))
      (node (ref "C278") (pin "1") (pinfunction "1_1") (pintype "passive"))
      (node (ref "C279") (pin "1") (pinfunction "1_1") (pintype "passive"))
      (node (ref "C280") (pin "1") (pinfunction "1_1") (pintype "passive"))
      (node (ref "C281") (pin "2") (pinfunction "2_2") (pintype "passive"))
      (node (ref "C303") (pin "2") (pinfunction "2_2") (pintype "passive"))
      (node (ref "C305") (pin "1") (pinfunction "1_1") (pintype "passive"))
      (node (ref "C306") (pin "1") (pinfunction "1_1") (pintype "passive"))
      (node (ref "C307") (pin "1") (pinfunction "1_1") (pintype "passive"))
      (node (ref "C322") (pin "2") (pinfunction "2_2") (pintype "passive"))
      (node (ref "D16") (pin "2") (pinfunction "A_2") (pintype "passive"))
      (node (ref "IC32") (pin "3") (pinfunction "VCC_3") (pintype "power_in"))
      (node (ref "IC34") (pin "3") (pinfunction "VCC_3") (pintype "power_in"))
      (node (ref "IC35") (pin "3") (pinfunction "VCC_3") (pintype "power_in"))
      (node (ref "IC39") (pin "3") (pinfunction "VCC_3") (pintype "power_in"))
      (node (ref "IC46") (pin "17") (pinfunction "VIN_17") (pintype "input"))
      (node (ref "IC46") (pin "24") (pinfunction "EN1_24") (pintype "input"))
      (node (ref "IC47") (pin "17") (pinfunction "VIN_17") (pintype "input"))
      (node (ref "IC48") (pin "3") (pinfunction "VCC_3") (pintype "power_in"))
      (node (ref "R243") (pin "2") (pinfunction "2_2") (pintype "passive"))
      (node (ref "T2") (pin "5") (pinfunction "D_5") (pintype "passive"))
      (node (ref "T2") (pin "6") (pinfunction "D_6") (pintype "passive"))
      (node (ref "T3") (pin "5") (pinfunction "D_5") (pintype "passive"))
      (node (ref "T3") (pin "6") (pinfunction "D_6") (pintype "passive"))
      (node (ref "T4") (pin "5") (pinfunction "D_5") (pintype "passive"))
      (node (ref "T4") (pin "6") (pinfunction "D_6") (pintype "passive"))
      (node (ref "T5") (pin "5") (pinfunction "D_5") (pintype "passive"))
      (node (ref "T5") (pin "6") (pinfunction "D_6") (pintype "passive"))
    )
    (net (code "14") (name "/+1V0_GTX_PG") (class "Default")
      (node (ref "IC39") (pin "2") (pinfunction "PG_2") (pintype "open_collector"))
      (node (ref "R207") (pin "2") (pinfunction "2_2") (pintype "passive"))
    )
    (net (code "15") (name "/+1V2_GTX_PG") (class "Default")
      (node (ref "IC32") (pin "2") (pinfunction "PG_2") (pintype "open_collector"))
      (node (ref "R181") (pin "2") (pinfunction "2_2") (pintype "passive"))
    )
    (net (code "16") (name "/+2V5_PLL_PG") (class "Default")
      (node (ref "IC34") (pin "2") (pinfunction "PG_2") (pintype "open_collector"))
      (node (ref "R190") (pin "2") (pinfunction "2_2") (pintype "passive"))
    )
    (net (code "17") (name "/+3V0_VM53_EN") (class "Default")
      (node (ref "IC44") (pin "3") (pinfunction "~{SHDN}_3") (pintype "input"))
      (node (ref "R211") (pin "1") (pinfunction "1_1") (pintype "passive"))
    )
    (net (code "18") (name "/+3V3_PG") (class "Default")
      (node (ref "IC48") (pin "2") (pinfunction "PG_2") (pintype "open_collector"))
      (node (ref "R239") (pin "2") (pinfunction "2_2") (pintype "passive"))
    )
    (net (code "19") (name "/+3V3_PLL_PG") (class "Default")
      (node (ref "IC35") (pin "2") (pinfunction "PG_2") (pintype "open_collector"))
      (node (ref "R191") (pin "2") (pinfunction "2_2") (pintype "passive"))
    )
    (net (code "20") (name "/LDO_IN") (class "Default")
      (node (ref "C277") (pin "1") (pinfunction "1_1") (pintype "passive"))
      (node (ref "C304") (pin "1") (pinfunction "1_1") (pintype "passive"))
      (node (ref "D16") (pin "1") (pinfunction "C_1") (pintype "passive"))
      (node (ref "IC35") (pin "1") (pinfunction "IN_1") (pintype "power_in"))
      (node (ref "IC48") (pin "1") (pinfunction "IN_1") (pintype "power_in"))
    )
    (net (code "22") (name "GND") (class "Default")
      (node (ref "C235") (pin "1") (pinfunction "1_1") (pintype "passive"))
      (node (ref "C236") (pin "1") (pinfunction "1_1") (pintype "passive"))
      (node (ref "C237") (pin "1") (pinfunction "1_1") (pintype "passive"))
      (node (ref "C238") (pin "2") (pinfunction "2_2") (pintype "passive"))
      (node (ref "C239") (pin "2") (pinfunction "2_2") (pintype "passive"))
      (node (ref "C245") (pin "1") (pinfunction "1_1") (pintype "passive"))
      (node (ref "C246") (pin "1") (pinfunction "1_1") (pintype "passive"))
      (node (ref "C247") (pin "1") (pinfunction "1_1") (pintype "passive"))
      (node (ref "C248") (pin "2") (pinfunction "2_2") (pintype "passive"))
      (node (ref "C249") (pin "2") (pinfunction "2_2") (pintype "passive"))
      (node (ref "C250") (pin "1") (pinfunction "1_1") (pintype "passive"))
      (node (ref "C251") (pin "1") (pinfunction "1_1") (pintype "passive"))
      (node (ref "C252") (pin "1") (pinfunction "1_1") (pintype "passive"))
      (node (ref "C254") (pin "2") (pinfunction "2_2") (pintype "passive"))
      (node (ref "C255") (pin "1") (pinfunction "1_1") (pintype "passive"))
      (node (ref "C256") (pin "2") (pinfunction "2_2") (pintype "passive"))
      (node (ref "C257") (pin "2") (pinfunction "2_2") (pintype "passive"))
      (node (ref "C258") (pin "2") (pinfunction "2_2") (pintype "passive"))
      (node (ref "C259") (pin "2") (pinfunction "2_2") (pintype "passive"))
      (node (ref "C260") (pin "2") (pinfunction "2_2") (pintype "passive"))
      (node (ref "C262") (pin "1") (pinfunction "1_1") (pintype "passive"))
      (node (ref "C263") (pin "1") (pinfunction "1_1") (pintype "passive"))
      (node (ref "C264") (pin "1") (pinfunction "1_1") (pintype "passive"))
      (node (ref "C265") (pin "1") (pinfunction "1_1") (pintype "passive"))
      (node (ref "C266") (pin "1") (pinfunction "1_1") (pintype "passive"))
      (node (ref "C267") (pin "1") (pinfunction "1_1") (pintype "passive"))
      (node (ref "C268") (pin "2") (pinfunction "2_2") (pintype "passive"))
      (node (ref "C269") (pin "1") (pinfunction "1_1") (pintype "passive"))
      (node (ref "C270") (pin "2") (pinfunction "2_2") (pintype "passive"))
      (node (ref "C271") (pin "2") (pinfunction "2_2") (pintype "passive"))
      (node (ref "C272") (pin "1") (pinfunction "1_1") (pintype "passive"))
      (node (ref "C273") (pin "2") (pinfunction "2_2") (pintype "passive"))
      (node (ref "C274") (pin "1") (pinfunction "1_1") (pintype "passive"))
      (node (ref "C275") (pin "2") (pinfunction "2_2") (pintype "passive"))
      (node (ref "C276") (pin "1") (pinfunction "1_1") (pintype "passive"))
      (node (ref "C277") (pin "2") (pinfunction "2_2") (pintype "passive"))
      (node (ref "C278") (pin "2") (pinfunction "2_2") (pintype "passive"))
      (node (ref "C279") (pin "2") (pinfunction "2_2") (pintype "passive"))
      (node (ref "C280") (pin "2") (pinfunction "2_2") (pintype "passive"))
      (node (ref "C281") (pin "1") (pinfunction "1_1") (pintype "passive"))
      (node (ref "C282") (pin "1") (pinfunction "1_1") (pintype "passive"))
      (node (ref "C283") (pin "1") (pinfunction "1_1") (pintype "passive"))
      (node (ref "C287") (pin "1") (pinfunction "1_1") (pintype "passive"))
      (node (ref "C288") (pin "2") (pinfunction "2_2") (pintype "passive"))
      (node (ref "C289") (pin "2") (pinfunction "2_2") (pintype "passive"))
      (node (ref "C290") (pin "2") (pinfunction "2_2") (pintype "passive"))
      (node (ref "C291") (pin "2") (pinfunction "2_2") (pintype "passive"))
      (node (ref "C292") (pin "2") (pinfunction "2_2") (pintype "passive"))
      (node (ref "C294") (pin "2") (pinfunction "2_2") (pintype "passive"))
      (node (ref "C295") (pin "1") (pinfunction "1_1") (pintype "passive"))
      (node (ref "C296") (pin "2") (pinfunction "2_2") (pintype "passive"))
      (node (ref "C297") (pin "1") (pinfunction "1_1") (pintype "passive"))
      (node (ref "C300") (pin "2") (pinfunction "2_2") (pintype "passive"))
      (node (ref "C301") (pin "2") (pinfunction "2_2") (pintype "passive"))
      (node (ref "C302") (pin "2") (pinfunction "2_2") (pintype "passive"))
      (node (ref "C303") (pin "1") (pinfunction "1_1") (pintype "passive"))
      (node (ref "C304") (pin "2") (pinfunction "2_2") (pintype "passive"))
      (node (ref "C305") (pin "2") (pinfunction "2_2") (pintype "passive"))
      (node (ref "C306") (pin "2") (pinfunction "2_2") (pintype "passive"))
      (node (ref "C307") (pin "2") (pinfunction "2_2") (pintype "passive"))
      (node (ref "C310") (pin "1") (pinfunction "1_1") (pintype "passive"))
      (node (ref "C311") (pin "1") (pinfunction "1_1") (pintype "passive"))
      (node (ref "C312") (pin "1") (pinfunction "1_1") (pintype "passive"))
      (node (ref "C322") (pin "1") (pinfunction "1_1") (pintype "passive"))
      (node (ref "C323") (pin "2") (pinfunction "2_2") (pintype "passive"))
      (node (ref "C427") (pin "2") (pinfunction "2_2") (pintype "passive"))
      (node (ref "C428") (pin "2") (pinfunction "2_2") (pintype "passive"))
      (node (ref "C429") (pin "2") (pinfunction "2_2") (pintype "passive"))
      (node (ref "C430") (pin "1") (pinfunction "1_1") (pintype "passive"))
      (node (ref "C431") (pin "2") (pinfunction "2_2") (pintype "passive"))
      (node (ref "C432") (pin "2") (pinfunction "2_2") (pintype "passive"))
      (node (ref "IC32") (pin "5") (pinfunction "GND_5") (pintype "power_in"))
      (node (ref "IC32") (pin "9") (pinfunction "TP_9") (pintype "power_in"))
      (node (ref "IC34") (pin "5") (pinfunction "GND_5") (pintype "power_in"))
      (node (ref "IC34") (pin "9") (pinfunction "TP_9") (pintype "power_in"))
      (node (ref "IC35") (pin "5") (pinfunction "GND_5") (pintype "power_in"))
      (node (ref "IC35") (pin "9") (pinfunction "TP_9") (pintype "power_in"))
      (node (ref "IC38") (pin "2") (pinfunction "VSS_2") (pintype "power_in"))
      (node (ref "IC39") (pin "5") (pinfunction "GND_5") (pintype "power_in"))
      (node (ref "IC39") (pin "9") (pinfunction "TP_9") (pintype "power_in"))
      (node (ref "IC44") (pin "2") (pinfunction "VSS_2") (pintype "power_in"))
      (node (ref "IC46") (pin "12") (pinfunction "PGND2_12") (pintype "power_in"))
      (node (ref "IC46") (pin "19") (pinfunction "PGND1_19") (pintype "power_in"))
      (node (ref "IC46") (pin "25") (pinfunction "EP_25") (pintype "power_in"))
      (node (ref "IC46") (pin "3") (pinfunction "GND_3") (pintype "power_in"))
      (node (ref "IC46") (pin "4") (pinfunction "TEST1_4") (pintype "bidirectional"))
      (node (ref "IC47") (pin "12") (pinfunction "PGND2_12") (pintype "power_in"))
      (node (ref "IC47") (pin "19") (pinfunction "PGND1_19") (pintype "power_in"))
      (node (ref "IC47") (pin "25") (pinfunction "EP_25") (pintype "power_in"))
      (node (ref "IC47") (pin "3") (pinfunction "GND_3") (pintype "power_in"))
      (node (ref "IC47") (pin "4") (pinfunction "TEST1_4") (pintype "bidirectional"))
      (node (ref "IC48") (pin "5") (pinfunction "GND_5") (pintype "power_in"))
      (node (ref "IC48") (pin "9") (pinfunction "TP_9") (pintype "power_in"))
      (node (ref "R178") (pin "1") (pinfunction "1_1") (pintype "passive"))
      (node (ref "R185") (pin "1") (pinfunction "1_1") (pintype "passive"))
      (node (ref "R186") (pin "1") (pinfunction "1_1") (pintype "passive"))
      (node (ref "R204") (pin "1") (pinfunction "1_1") (pintype "passive"))
      (node (ref "R209") (pin "2") (pinfunction "2_2") (pintype "passive"))
      (node (ref "R227") (pin "1") (pinfunction "1_1") (pintype "passive"))
      (node (ref "R229") (pin "2") (pinfunction "2_2") (pintype "passive"))
      (node (ref "R231") (pin "2") (pinfunction "2_2") (pintype "passive"))
      (node (ref "R232") (pin "2") (pinfunction "2_2") (pintype "passive"))
      (node (ref "R234") (pin "2") (pinfunction "2_2") (pintype "passive"))
      (node (ref "R235") (pin "1") (pinfunction "1_1") (pintype "passive"))
      (node (ref "R236") (pin "1") (pinfunction "1_1") (pintype "passive"))
      (node (ref "R238") (pin "2") (pinfunction "2_2") (pintype "passive"))
      (node (ref "R240") (pin "2") (pinfunction "2_2") (pintype "passive"))
      (node (ref "R242") (pin "2") (pinfunction "2_2") (pintype "passive"))
      (node (ref "T2") (pin "1") (pinfunction "S_1") (pintype "passive"))
      (node (ref "T3") (pin "1") (pinfunction "S_1") (pintype "passive"))
      (node (ref "T4") (pin "1") (pinfunction "S_1") (pintype "passive"))
      (node (ref "T5") (pin "1") (pinfunction "S_1") (pintype "passive"))
    )
    (net (code "23") (name "Net-(D3-A)") (class "Default")
      (node (ref "D3") (pin "1") (pinfunction "A_1") (pintype "passive"))
      (node (ref "IC47") (pin "7") (pinfunction "EN2_7") (pintype "input"))
      (node (ref "R243") (pin "1") (pinfunction "1_1") (pintype "passive"))
    )
    (net (code "24") (name "Net-(D3-K)") (class "Default")
      (node (ref "D3") (pin "2") (pinfunction "K_2") (pintype "passive"))
      (node (ref "D4") (pin "1") (pinfunction "A_1") (pintype "passive"))
    )
    (net (code "25") (name "Net-(IC32-FB)") (class "Default")
      (node (ref "IC32") (pin "7") (pinfunction "FB_7") (pintype "passive"))
      (node (ref "R178") (pin "2") (pinfunction "2_2") (pintype "passive"))
      (node (ref "R180") (pin "1") (pinfunction "1_1") (pintype "passive"))
    )
    (net (code "26") (name "Net-(IC32-SS)") (class "Default")
      (node (ref "C245") (pin "2") (pinfunction "2_2") (pintype "passive"))
      (node (ref "IC32") (pin "6") (pinfunction "SS_6") (pintype "passive"))
    )
    (net (code "27") (name "Net-(IC34-FB)") (class "Default")
      (node (ref "IC34") (pin "7") (pinfunction "FB_7") (pintype "passive"))
      (node (ref "R185") (pin "2") (pinfunction "2_2") (pintype "passive"))
      (node (ref "R188") (pin "2") (pinfunction "2_2") (pintype "passive"))
    )
    (net (code "28") (name "Net-(IC34-SS)") (class "Default")
      (node (ref "C262") (pin "2") (pinfunction "2_2") (pintype "passive"))
      (node (ref "IC34") (pin "6") (pinfunction "SS_6") (pintype "passive"))
    )
    (net (code "29") (name "Net-(IC35-FB)") (class "Default")
      (node (ref "IC35") (pin "7") (pinfunction "FB_7") (pintype "passive"))
      (node (ref "R186") (pin "2") (pinfunction "2_2") (pintype "passive"))
      (node (ref "R189") (pin "2") (pinfunction "2_2") (pintype "passive"))
    )
    (net (code "30") (name "Net-(IC35-SS)") (class "Default")
      (node (ref "C265") (pin "2") (pinfunction "2_2") (pintype "passive"))
      (node (ref "IC35") (pin "6") (pinfunction "SS_6") (pintype "passive"))
    )
    (net (code "31") (name "Net-(IC39-FB)") (class "Default")
      (node (ref "IC39") (pin "7") (pinfunction "FB_7") (pintype "passive"))
      (node (ref "R204") (pin "2") (pinfunction "2_2") (pintype "passive"))
      (node (ref "R205") (pin "1") (pinfunction "1_1") (pintype "passive"))
    )
    (net (code "32") (name "Net-(IC39-SS)") (class "Default")
      (node (ref "C310") (pin "2") (pinfunction "2_2") (pintype "passive"))
      (node (ref "IC39") (pin "6") (pinfunction "SS_6") (pintype "passive"))
    )
    (net (code "33") (name "Net-(IC46-DRVH1)") (class "Default")
      (node (ref "IC46") (pin "22") (pinfunction "DRVH1_22") (pintype "output"))
      (node (ref "T3") (pin "4") (pinfunction "G_4") (pintype "passive"))
    )
    (net (code "34") (name "Net-(IC46-DRVH2)") (class "Default")
      (node (ref "IC46") (pin "9") (pinfunction "DRVH2_9") (pintype "output"))
      (node (ref "T2") (pin "4") (pinfunction "G_4") (pintype "passive"))
    )
    (net (code "35") (name "Net-(IC46-DRVL1)") (class "Default")
      (node (ref "IC46") (pin "20") (pinfunction "DRVL1_20") (pintype "output"))
      (node (ref "T3") (pin "2") (pinfunction "G_2") (pintype "passive"))
    )
    (net (code "36") (name "Net-(IC46-DRVL2)") (class "Default")
      (node (ref "IC46") (pin "11") (pinfunction "DRVL2_11") (pintype "output"))
      (node (ref "T2") (pin "2") (pinfunction "G_2") (pintype "passive"))
    )
    (net (code "37") (name "Net-(IC46-SW1)") (class "Default")
      (node (ref "C253") (pin "2") (pinfunction "2_2") (pintype "passive"))
      (node (ref "IC46") (pin "21") (pinfunction "SW1_21") (pintype "bidirectional"))
      (node (ref "L13") (pin "1") (pinfunction "1_1") (pintype "passive"))
      (node (ref "T3") (pin "3") (pinfunction "S_3") (pintype "passive"))
      (node (ref "T3") (pin "7") (pinfunction "D_7") (pintype "passive"))
      (node (ref "T3") (pin "8") (pinfunction "D_8") (pintype "passive"))
    )
    (net (code "38") (name "Net-(IC46-SW2)") (class "Default")
      (node (ref "C207") (pin "2") (pinfunction "2_2") (pintype "passive"))
      (node (ref "IC46") (pin "10") (pinfunction "SW2_10") (pintype "bidirectional"))
      (node (ref "L11") (pin "1") (pinfunction "1_1") (pintype "passive"))
      (node (ref "T2") (pin "3") (pinfunction "S_3") (pintype "passive"))
      (node (ref "T2") (pin "7") (pinfunction "D_7") (pintype "passive"))
      (node (ref "T2") (pin "8") (pinfunction "D_8") (pintype "passive"))
    )
    (net (code "39") (name "Net-(IC46-TEST2)") (class "Default")
      (node (ref "IC46") (pin "14") (pinfunction "TEST2_14") (pintype "input"))
      (node (ref "R210") (pin "2") (pinfunction "2_2") (pintype "passive"))
      (node (ref "R227") (pin "2") (pinfunction "2_2") (pintype "passive"))
    )
    (net (code "40") (name "Net-(IC46-TRIP1)") (class "Default")
      (node (ref "IC46") (pin "18") (pinfunction "TRIP1_18") (pintype "input"))
      (node (ref "R229") (pin "1") (pinfunction "1_1") (pintype "passive"))
    )
    (net (code "41") (name "Net-(IC46-TRIP2)") (class "Default")
      (node (ref "IC46") (pin "13") (pinfunction "TRIP2_13") (pintype "input"))
      (node (ref "R209") (pin "1") (pinfunction "1_1") (pintype "passive"))
    )
    (net (code "42") (name "Net-(IC46-V5FILT)") (class "Default")
      (node (ref "C237") (pin "2") (pinfunction "2_2") (pintype "passive"))
      (node (ref "IC46") (pin "15") (pinfunction "V5FILT_15") (pintype "input"))
      (node (ref "R210") (pin "1") (pinfunction "1_1") (pintype "passive"))
    )
    (net (code "43") (name "Net-(IC46-VBST1)") (class "Default")
      (node (ref "C253") (pin "1") (pinfunction "1_1") (pintype "passive"))
      (node (ref "IC46") (pin "23") (pinfunction "VBST1_23") (pintype "input"))
    )
    (net (code "44") (name "Net-(IC46-VBST2)") (class "Default")
      (node (ref "C207") (pin "1") (pinfunction "1_1") (pintype "passive"))
      (node (ref "IC46") (pin "8") (pinfunction "VBST2_8") (pintype "input"))
    )
    (net (code "45") (name "Net-(IC46-VFB1)") (class "Default")
      (node (ref "IC46") (pin "2") (pinfunction "VFB1_2") (pintype "input"))
      (node (ref "R230") (pin "1") (pinfunction "1_1") (pintype "passive"))
      (node (ref "R231") (pin "1") (pinfunction "1_1") (pintype "passive"))
    )
    (net (code "46") (name "Net-(IC46-VFB2)") (class "Default")
      (node (ref "IC46") (pin "5") (pinfunction "VFB2_5") (pintype "input"))
      (node (ref "R228") (pin "2") (pinfunction "2_2") (pintype "passive"))
      (node (ref "R238") (pin "1") (pinfunction "1_1") (pintype "passive"))
    )
    (net (code "47") (name "Net-(IC46-VREG5)") (class "Default")
      (node (ref "C238") (pin "1") (pinfunction "1_1") (pintype "passive"))
      (node (ref "IC46") (pin "16") (pinfunction "VREG5_16") (pintype "output"))
    )
    (net (code "48") (name "Net-(IC47-DRVH1)") (class "Default")
      (node (ref "IC47") (pin "22") (pinfunction "DRVH1_22") (pintype "output"))
      (node (ref "T5") (pin "4") (pinfunction "G_4") (pintype "passive"))
    )
    (net (code "49") (name "Net-(IC47-DRVH2)") (class "Default")
      (node (ref "IC47") (pin "9") (pinfunction "DRVH2_9") (pintype "output"))
      (node (ref "T4") (pin "4") (pinfunction "G_4") (pintype "passive"))
    )
    (net (code "50") (name "Net-(IC47-DRVL1)") (class "Default")
      (node (ref "IC47") (pin "20") (pinfunction "DRVL1_20") (pintype "output"))
      (node (ref "T5") (pin "2") (pinfunction "G_2") (pintype "passive"))
    )
    (net (code "51") (name "Net-(IC47-DRVL2)") (class "Default")
      (node (ref "IC47") (pin "11") (pinfunction "DRVL2_11") (pintype "output"))
      (node (ref "T4") (pin "2") (pinfunction "G_2") (pintype "passive"))
    )
    (net (code "52") (name "Net-(IC47-SW1)") (class "Default")
      (node (ref "C293") (pin "2") (pinfunction "2_2") (pintype "passive"))
      (node (ref "IC47") (pin "21") (pinfunction "SW1_21") (pintype "bidirectional"))
      (node (ref "L15") (pin "1") (pinfunction "1_1") (pintype "passive"))
      (node (ref "T5") (pin "3") (pinfunction "S_3") (pintype "passive"))
      (node (ref "T5") (pin "7") (pinfunction "D_7") (pintype "passive"))
      (node (ref "T5") (pin "8") (pinfunction "D_8") (pintype "passive"))
    )
    (net (code "53") (name "Net-(IC47-SW2)") (class "Default")
      (node (ref "C261") (pin "2") (pinfunction "2_2") (pintype "passive"))
      (node (ref "IC47") (pin "10") (pinfunction "SW2_10") (pintype "bidirectional"))
      (node (ref "L14") (pin "1") (pinfunction "1_1") (pintype "passive"))
      (node (ref "T4") (pin "3") (pinfunction "S_3") (pintype "passive"))
      (node (ref "T4") (pin "7") (pinfunction "D_7") (pintype "passive"))
      (node (ref "T4") (pin "8") (pinfunction "D_8") (pintype "passive"))
    )
    (net (code "54") (name "Net-(IC47-TEST2)") (class "Default")
      (node (ref "IC47") (pin "14") (pinfunction "TEST2_14") (pintype "input"))
      (node (ref "R233") (pin "2") (pinfunction "2_2") (pintype "passive"))
      (node (ref "R235") (pin "2") (pinfunction "2_2") (pintype "passive"))
    )
    (net (code "55") (name "Net-(IC47-TRIP1)") (class "Default")
      (node (ref "IC47") (pin "18") (pinfunction "TRIP1_18") (pintype "input"))
      (node (ref "R240") (pin "1") (pinfunction "1_1") (pintype "passive"))
    )
    (net (code "56") (name "Net-(IC47-TRIP2)") (class "Default")
      (node (ref "IC47") (pin "13") (pinfunction "TRIP2_13") (pintype "input"))
      (node (ref "R232") (pin "1") (pinfunction "1_1") (pintype "passive"))
    )
    (net (code "57") (name "Net-(IC47-V5FILT)") (class "Default")
      (node (ref "C272") (pin "2") (pinfunction "2_2") (pintype "passive"))
      (node (ref "IC47") (pin "15") (pinfunction "V5FILT_15") (pintype "input"))
      (node (ref "R233") (pin "1") (pinfunction "1_1") (pintype "passive"))
    )
    (net (code "58") (name "Net-(IC47-VBST1)") (class "Default")
      (node (ref "C293") (pin "1") (pinfunction "1_1") (pintype "passive"))
      (node (ref "IC47") (pin "23") (pinfunction "VBST1_23") (pintype "input"))
    )
    (net (code "59") (name "Net-(IC47-VBST2)") (class "Default")
      (node (ref "C261") (pin "1") (pinfunction "1_1") (pintype "passive"))
      (node (ref "IC47") (pin "8") (pinfunction "VBST2_8") (pintype "input"))
    )
    (net (code "60") (name "Net-(IC47-VFB1)") (class "Default")
      (node (ref "IC47") (pin "2") (pinfunction "VFB1_2") (pintype "input"))
      (node (ref "R241") (pin "1") (pinfunction "1_1") (pintype "passive"))
      (node (ref "R242") (pin "1") (pinfunction "1_1") (pintype "passive"))
    )
    (net (code "61") (name "Net-(IC47-VFB2)") (class "Default")
      (node (ref "IC47") (pin "5") (pinfunction "VFB2_5") (pintype "input"))
      (node (ref "R206") (pin "1") (pinfunction "1_1") (pintype "passive"))
      (node (ref "R234") (pin "1") (pinfunction "1_1") (pintype "passive"))
    )
    (net (code "62") (name "Net-(IC47-VREG5)") (class "Default")
      (node (ref "C273") (pin "1") (pinfunction "1_1") (pintype "passive"))
      (node (ref "IC47") (pin "16") (pinfunction "VREG5_16") (pintype "output"))
    )
    (net (code "63") (name "Net-(IC48-FB)") (class "Default")
      (node (ref "IC48") (pin "7") (pinfunction "FB_7") (pintype "passive"))
      (node (ref "R236") (pin "2") (pinfunction "2_2") (pintype "passive"))
      (node (ref "R237") (pin "1") (pinfunction "1_1") (pintype "passive"))
    )
    (net (code "64") (name "Net-(IC48-SS)") (class "Default")
      (node (ref "C282") (pin "2") (pinfunction "2_2") (pintype "passive"))
      (node (ref "IC48") (pin "6") (pinfunction "SS_6") (pintype "passive"))
    )
    (net (code "65") (name "unconnected-(IC38-NC-Pad4)") (class "Default")
      (node (ref "IC38") (pin "4") (pinfunction "NC_4") (pintype "passive+no_connect"))
    )
    (net (code "66") (name "unconnected-(IC44-NC-Pad4)") (class "Default")
      (node (ref "IC44") (pin "4") (pinfunction "NC_4") (pintype "passive+no_connect"))
    )
  )
)
